# iobaord.net
KiCad netlist of a schematic drawn in EAGLE
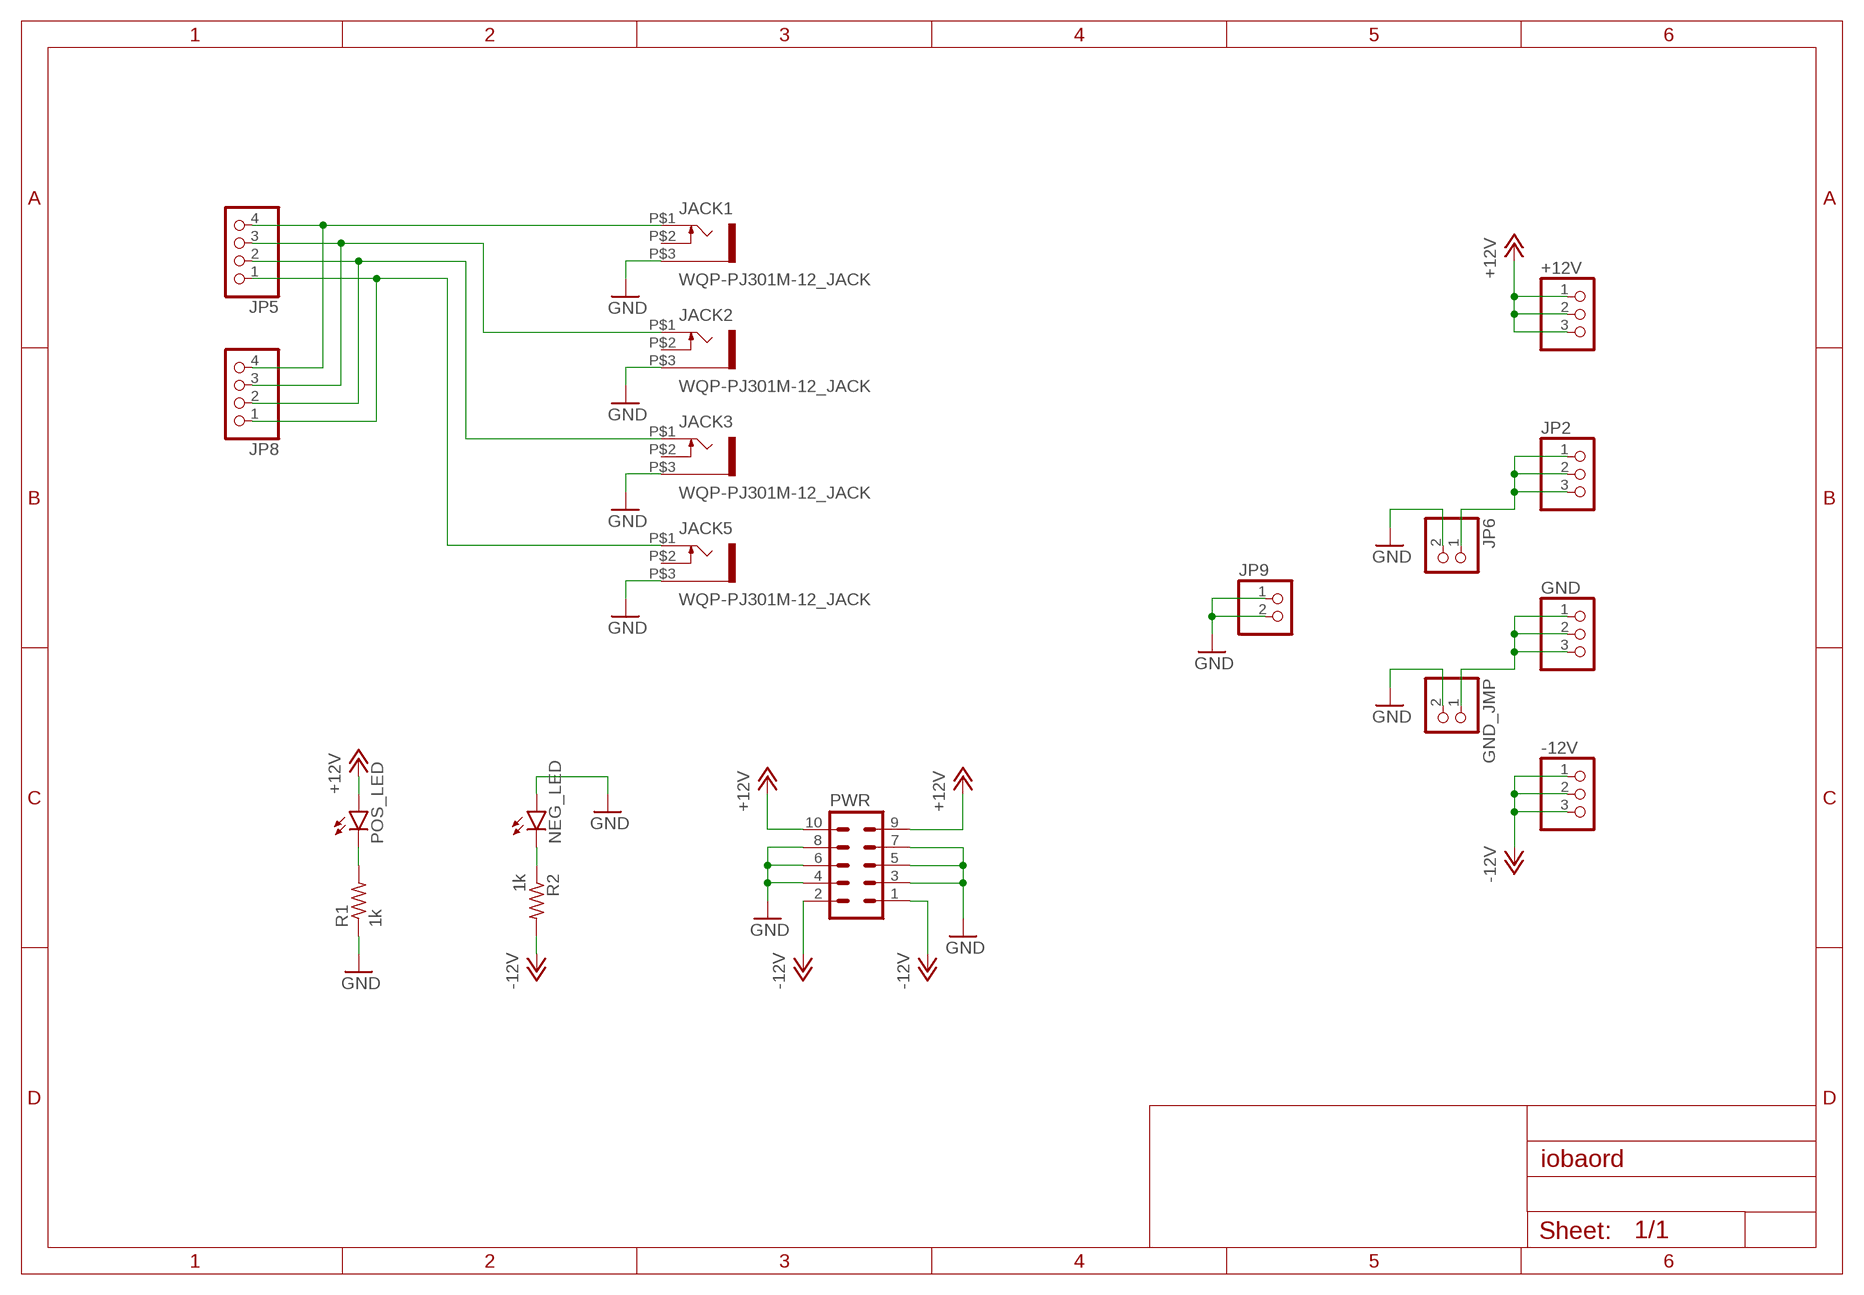
[diagram p0: schematic, sheet 1]

(export (version "E")
  (design (tool "Eeschema 10.0.6"))
  (components
    (comp (ref "+12V")
      (value "PINHD-1X3")
      (footprint "eagle-import:1X03")
      (libsource (lib "eagle-import") (part "PINHD-1X3"))
    )
    (comp (ref "-12V")
      (value "PINHD-1X3")
      (footprint "eagle-import:1X03")
      (libsource (lib "eagle-import") (part "PINHD-1X3"))
    )
    (comp (ref "GND")
      (value "PINHD-1X3")
      (footprint "eagle-import:1X03")
      (libsource (lib "eagle-import") (part "PINHD-1X3"))
    )
    (comp (ref "GND_JMP")
      (value "PINHD-1X2")
      (footprint "eagle-import:1X02")
      (libsource (lib "eagle-import") (part "PINHD-1X2"))
    )
    (comp (ref "JACK1")
      (value "WQP-PJ301M-12_JACK")
      (footprint "eagle-import:WQP-PJ301M-12_JACK")
      (libsource (lib "eagle-import") (part "WQP-PJ301M-12_JACK"))
    )
    (comp (ref "JACK2")
      (value "WQP-PJ301M-12_JACK")
      (footprint "eagle-import:WQP-PJ301M-12_JACK")
      (libsource (lib "eagle-import") (part "WQP-PJ301M-12_JACK"))
    )
    (comp (ref "JACK3")
      (value "WQP-PJ301M-12_JACK")
      (footprint "eagle-import:WQP-PJ301M-12_JACK")
      (libsource (lib "eagle-import") (part "WQP-PJ301M-12_JACK"))
    )
    (comp (ref "JACK5")
      (value "WQP-PJ301M-12_JACK")
      (footprint "eagle-import:WQP-PJ301M-12_JACK")
      (libsource (lib "eagle-import") (part "WQP-PJ301M-12_JACK"))
    )
    (comp (ref "JP2")
      (value "PINHD-1X3")
      (footprint "eagle-import:1X03")
      (libsource (lib "eagle-import") (part "PINHD-1X3"))
    )
    (comp (ref "JP5")
      (value "PINHD-1X4")
      (footprint "eagle-import:1X04")
      (libsource (lib "eagle-import") (part "PINHD-1X4"))
    )
    (comp (ref "JP6")
      (value "PINHD-1X2")
      (footprint "eagle-import:1X02")
      (libsource (lib "eagle-import") (part "PINHD-1X2"))
    )
    (comp (ref "JP8")
      (value "PINHD-1X4")
      (footprint "eagle-import:1X04")
      (libsource (lib "eagle-import") (part "PINHD-1X4"))
    )
    (comp (ref "JP9")
      (value "PINHD-1X2")
      (footprint "eagle-import:1X02")
      (libsource (lib "eagle-import") (part "PINHD-1X2"))
    )
    (comp (ref "NEG_LED")
      (value "LED3MM")
      (footprint "eagle-import:LED3MM")
      (libsource (lib "eagle-import") (part "LED3MM"))
    )
    (comp (ref "POS_LED")
      (value "LED3MM")
      (footprint "eagle-import:LED3MM")
      (libsource (lib "eagle-import") (part "LED3MM"))
    )
    (comp (ref "PWR")
      (value "ML10")
      (footprint "eagle-import:ML10")
      (libsource (lib "eagle-import") (part "ML10"))
    )
    (comp (ref "R1")
      (value "1k")
      (footprint "eagle-import:0207_7")
      (libsource (lib "eagle-import") (part "R-US_0207/7"))
    )
    (comp (ref "R2")
      (value "1k")
      (footprint "eagle-import:0207_7")
      (libsource (lib "eagle-import") (part "R-US_0207/7"))
    )
  )
  (nets
    (net (code "1") (name "+12V") (class "Default")
      (node (ref "+12V") (pin "1") (pinfunction "1_1") (pintype "passive"))
      (node (ref "+12V") (pin "2") (pinfunction "2_2") (pintype "passive"))
      (node (ref "+12V") (pin "3") (pinfunction "3_3") (pintype "passive"))
      (node (ref "POS_LED") (pin "A") (pinfunction "A_A") (pintype "passive"))
      (node (ref "PWR") (pin "10") (pinfunction "10_10") (pintype "passive"))
      (node (ref "PWR") (pin "9") (pinfunction "9_9") (pintype "passive"))
    )
    (net (code "2") (name "-12V") (class "Default")
      (node (ref "-12V") (pin "1") (pinfunction "1_1") (pintype "passive"))
      (node (ref "-12V") (pin "2") (pinfunction "2_2") (pintype "passive"))
      (node (ref "-12V") (pin "3") (pinfunction "3_3") (pintype "passive"))
      (node (ref "PWR") (pin "1") (pinfunction "1_1") (pintype "passive"))
      (node (ref "PWR") (pin "2") (pinfunction "2_2") (pintype "passive"))
      (node (ref "R2") (pin "2") (pinfunction "2_2") (pintype "passive"))
    )
    (net (code "3") (name "GND") (class "Default")
      (node (ref "GND_JMP") (pin "2") (pinfunction "2_2") (pintype "passive"))
      (node (ref "JACK1") (pin "P$3") (pinfunction "1_P$3") (pintype "passive"))
      (node (ref "JACK2") (pin "P$3") (pinfunction "1_P$3") (pintype "passive"))
      (node (ref "JACK3") (pin "P$3") (pinfunction "1_P$3") (pintype "passive"))
      (node (ref "JACK5") (pin "P$3") (pinfunction "1_P$3") (pintype "passive"))
      (node (ref "JP6") (pin "2") (pinfunction "2_2") (pintype "passive"))
      (node (ref "JP9") (pin "1") (pinfunction "1_1") (pintype "passive"))
      (node (ref "JP9") (pin "2") (pinfunction "2_2") (pintype "passive"))
      (node (ref "NEG_LED") (pin "A") (pinfunction "A_A") (pintype "passive"))
      (node (ref "PWR") (pin "3") (pinfunction "3_3") (pintype "passive"))
      (node (ref "PWR") (pin "4") (pinfunction "4_4") (pintype "passive"))
      (node (ref "PWR") (pin "5") (pinfunction "5_5") (pintype "passive"))
      (node (ref "PWR") (pin "6") (pinfunction "6_6") (pintype "passive"))
      (node (ref "PWR") (pin "7") (pinfunction "7_7") (pintype "passive"))
      (node (ref "PWR") (pin "8") (pinfunction "8_8") (pintype "passive"))
      (node (ref "R1") (pin "1") (pinfunction "1_1") (pintype "passive"))
    )
    (net (code "4") (name "Net-(GND-Pad1)") (class "Default")
      (node (ref "GND") (pin "1") (pinfunction "1_1") (pintype "passive"))
      (node (ref "GND") (pin "2") (pinfunction "2_2") (pintype "passive"))
      (node (ref "GND") (pin "3") (pinfunction "3_3") (pintype "passive"))
      (node (ref "GND_JMP") (pin "1") (pinfunction "1_1") (pintype "passive"))
    )
    (net (code "5") (name "Net-(JACK1-2)") (class "Default")
      (node (ref "JACK1") (pin "P$1") (pinfunction "2_P$1") (pintype "passive"))
      (node (ref "JP5") (pin "4") (pinfunction "4_4") (pintype "passive"))
      (node (ref "JP8") (pin "4") (pinfunction "4_4") (pintype "passive"))
    )
    (net (code "6") (name "Net-(JACK2-2)") (class "Default")
      (node (ref "JACK2") (pin "P$1") (pinfunction "2_P$1") (pintype "passive"))
      (node (ref "JP5") (pin "3") (pinfunction "3_3") (pintype "passive"))
      (node (ref "JP8") (pin "3") (pinfunction "3_3") (pintype "passive"))
    )
    (net (code "7") (name "Net-(JACK3-2)") (class "Default")
      (node (ref "JACK3") (pin "P$1") (pinfunction "2_P$1") (pintype "passive"))
      (node (ref "JP5") (pin "2") (pinfunction "2_2") (pintype "passive"))
      (node (ref "JP8") (pin "2") (pinfunction "2_2") (pintype "passive"))
    )
    (net (code "8") (name "Net-(JACK5-2)") (class "Default")
      (node (ref "JACK5") (pin "P$1") (pinfunction "2_P$1") (pintype "passive"))
      (node (ref "JP5") (pin "1") (pinfunction "1_1") (pintype "passive"))
      (node (ref "JP8") (pin "1") (pinfunction "1_1") (pintype "passive"))
    )
    (net (code "9") (name "Net-(JP2-Pad1)") (class "Default")
      (node (ref "JP2") (pin "1") (pinfunction "1_1") (pintype "passive"))
      (node (ref "JP2") (pin "2") (pinfunction "2_2") (pintype "passive"))
      (node (ref "JP2") (pin "3") (pinfunction "3_3") (pintype "passive"))
      (node (ref "JP6") (pin "1") (pinfunction "1_1") (pintype "passive"))
    )
    (net (code "10") (name "Net-(NEG_LED-C)") (class "Default")
      (node (ref "NEG_LED") (pin "K") (pinfunction "C_K") (pintype "passive"))
      (node (ref "R2") (pin "1") (pinfunction "1_1") (pintype "passive"))
    )
    (net (code "11") (name "Net-(POS_LED-C)") (class "Default")
      (node (ref "POS_LED") (pin "K") (pinfunction "C_K") (pintype "passive"))
      (node (ref "R1") (pin "2") (pinfunction "2_2") (pintype "passive"))
    )
    (net (code "12") (name "unconnected-(JACK1-3-PadP$2)") (class "Default")
      (node (ref "JACK1") (pin "P$2") (pinfunction "3_P$2") (pintype "passive"))
    )
    (net (code "13") (name "unconnected-(JACK2-3-PadP$2)") (class "Default")
      (node (ref "JACK2") (pin "P$2") (pinfunction "3_P$2") (pintype "passive"))
    )
    (net (code "14") (name "unconnected-(JACK3-3-PadP$2)") (class "Default")
      (node (ref "JACK3") (pin "P$2") (pinfunction "3_P$2") (pintype "passive"))
    )
    (net (code "15") (name "unconnected-(JACK5-3-PadP$2)") (class "Default")
      (node (ref "JACK5") (pin "P$2") (pinfunction "3_P$2") (pintype "passive"))
    )
  )
)
